# switch_board.net
KiCad netlist of a schematic drawn in EAGLE
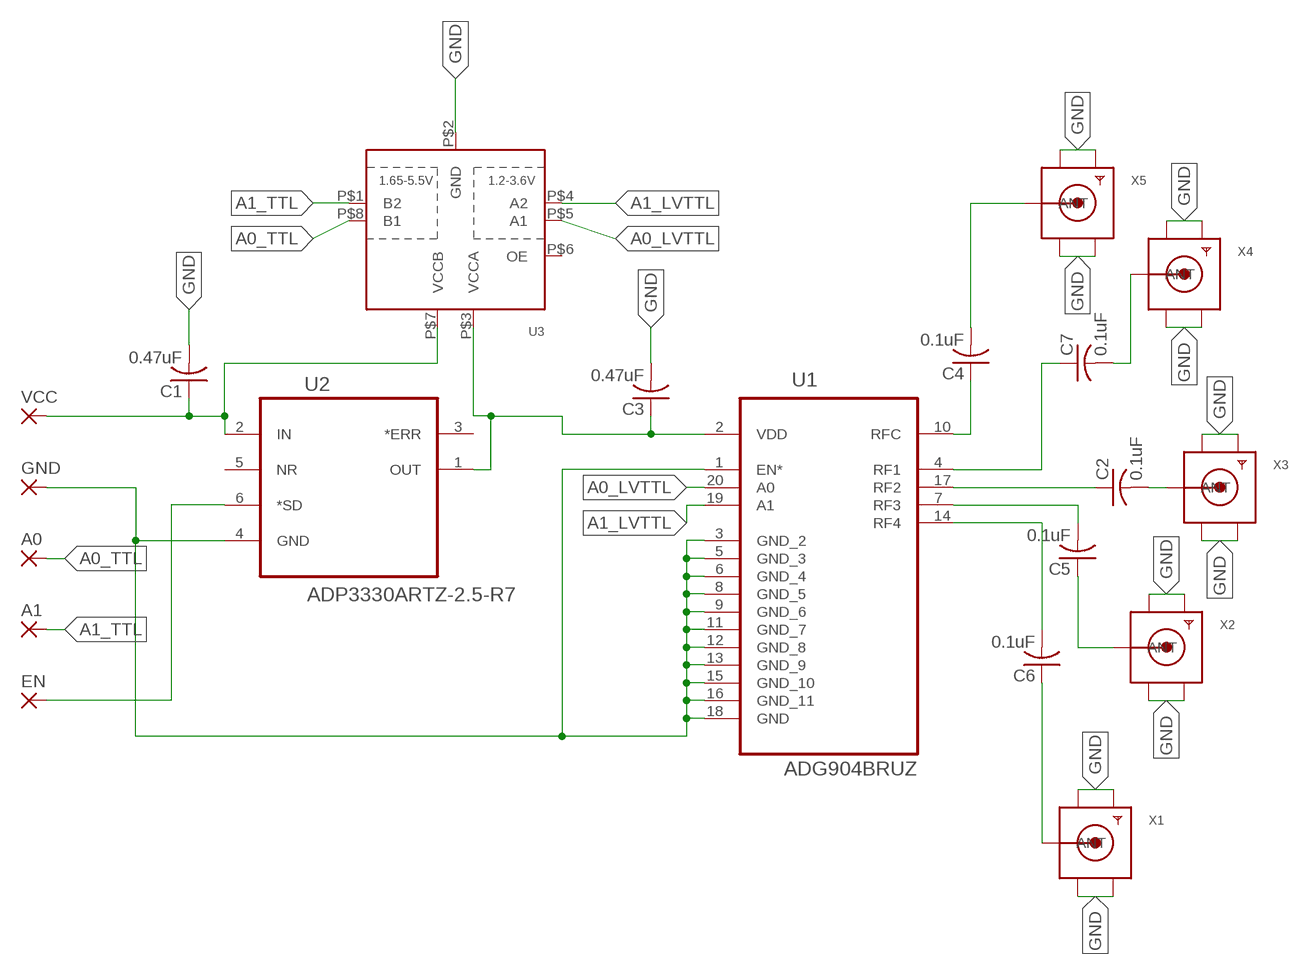
[diagram p0: schematic, sheet 1]

(export (version "E")
  (design (tool "Eeschema 10.0.6"))
  (components
    (comp (ref "A0")
      (value "2,54/1,0")
      (footprint "eagle-import:2,54_1,0")
      (libsource (lib "eagle-import") (part "2,54/1,0"))
    )
    (comp (ref "A1")
      (value "2,54/1,0")
      (footprint "eagle-import:2,54_1,0")
      (libsource (lib "eagle-import") (part "2,54/1,0"))
    )
    (comp (ref "C1")
      (value "0.47uF")
      (footprint "eagle-import:C0603")
      (libsource (lib "eagle-import") (part "C-USC0603"))
    )
    (comp (ref "C2")
      (value "0.1uF")
      (footprint "eagle-import:C0603")
      (libsource (lib "eagle-import") (part "C-USC0603"))
    )
    (comp (ref "C3")
      (value "0.47uF")
      (footprint "eagle-import:C0603")
      (libsource (lib "eagle-import") (part "C-USC0603"))
    )
    (comp (ref "C4")
      (value "0.1uF")
      (footprint "eagle-import:C0603")
      (libsource (lib "eagle-import") (part "C-USC0603"))
    )
    (comp (ref "C5")
      (value "0.1uF")
      (footprint "eagle-import:C0603")
      (libsource (lib "eagle-import") (part "C-USC0603"))
    )
    (comp (ref "C6")
      (value "0.1uF")
      (footprint "eagle-import:C0603")
      (libsource (lib "eagle-import") (part "C-USC0603"))
    )
    (comp (ref "C7")
      (value "0.1uF")
      (footprint "eagle-import:C0603")
      (libsource (lib "eagle-import") (part "C-USC0603"))
    )
    (comp (ref "EN")
      (value "2,54/1,0")
      (footprint "eagle-import:2,54_1,0")
      (libsource (lib "eagle-import") (part "2,54/1,0"))
    )
    (comp (ref "GND")
      (value "2,54/1,0")
      (footprint "eagle-import:2,54_1,0")
      (libsource (lib "eagle-import") (part "2,54/1,0"))
    )
    (comp (ref "U1")
      (value "ADG904BRUZ")
      (footprint "eagle-import:SOP65P640X120-20N")
      (libsource (lib "eagle-import") (part "ADG904BRUZ"))
    )
    (comp (ref "U2")
      (value "ADP3330ARTZ-2.5-R7")
      (footprint "eagle-import:SOT95P280X145-6N")
      (libsource (lib "eagle-import") (part "ADP3330ARTZ-2.5-R7"))
    )
    (comp (ref "U3")
      (value "TXS0102")
      (footprint "eagle-import:VFSOP-8")
      (libsource (lib "eagle-import") (part "TXS0102"))
    )
    (comp (ref "VCC")
      (value "2,54/1,0")
      (footprint "eagle-import:2,54_1,0")
      (libsource (lib "eagle-import") (part "2,54/1,0"))
    )
    (comp (ref "X1")
      (value "SMACONNECTOR_EDGE")
      (footprint "eagle-import:SMA_EDGELAUNCH")
      (libsource (lib "eagle-import") (part "SMACONNECTOR_EDGE"))
    )
    (comp (ref "X2")
      (value "SMACONNECTOR_EDGE")
      (footprint "eagle-import:SMA_EDGELAUNCH")
      (libsource (lib "eagle-import") (part "SMACONNECTOR_EDGE"))
    )
    (comp (ref "X3")
      (value "SMACONNECTOR_EDGE")
      (footprint "eagle-import:SMA_EDGELAUNCH")
      (libsource (lib "eagle-import") (part "SMACONNECTOR_EDGE"))
    )
    (comp (ref "X4")
      (value "SMACONNECTOR_EDGE")
      (footprint "eagle-import:SMA_EDGELAUNCH")
      (libsource (lib "eagle-import") (part "SMACONNECTOR_EDGE"))
    )
    (comp (ref "X5")
      (value "SMACONNECTOR_EDGE")
      (footprint "eagle-import:SMA_EDGELAUNCH")
      (libsource (lib "eagle-import") (part "SMACONNECTOR_EDGE"))
    )
  )
  (nets
    (net (code "1") (name "A0_LVTTL") (class "Default")
      (node (ref "U1") (pin "20") (pinfunction "A0_20") (pintype "passive"))
      (node (ref "U3") (pin "P$5") (pinfunction "A1_P$5") (pintype "bidirectional"))
    )
    (net (code "2") (name "A0_TTL") (class "Default")
      (node (ref "A0") (pin "1") (pinfunction "P_1") (pintype "passive"))
      (node (ref "U3") (pin "P$8") (pinfunction "B1_P$8") (pintype "bidirectional"))
    )
    (net (code "3") (name "A1_LVTTL") (class "Default")
      (node (ref "U1") (pin "19") (pinfunction "A1_19") (pintype "passive"))
      (node (ref "U3") (pin "P$4") (pinfunction "A2_P$4") (pintype "bidirectional"))
    )
    (net (code "4") (name "A1_TTL") (class "Default")
      (node (ref "A1") (pin "1") (pinfunction "P_1") (pintype "passive"))
      (node (ref "U3") (pin "P$1") (pinfunction "B2_P$1") (pintype "bidirectional"))
    )
    (net (code "5") (name "GND") (class "Default")
      (node (ref "C1") (pin "2") (pinfunction "2_2") (pintype "passive"))
      (node (ref "C3") (pin "2") (pinfunction "2_2") (pintype "passive"))
      (node (ref "GND") (pin "1") (pinfunction "P_1") (pintype "passive"))
      (node (ref "U1") (pin "1") (pinfunction "EN*_1") (pintype "passive"))
      (node (ref "U1") (pin "11") (pinfunction "GND_7_11") (pintype "passive"))
      (node (ref "U1") (pin "12") (pinfunction "GND_8_12") (pintype "passive"))
      (node (ref "U1") (pin "13") (pinfunction "GND_9_13") (pintype "passive"))
      (node (ref "U1") (pin "15") (pinfunction "GND_10_15") (pintype "passive"))
      (node (ref "U1") (pin "16") (pinfunction "GND_11_16") (pintype "passive"))
      (node (ref "U1") (pin "18") (pinfunction "GND_18") (pintype "passive"))
      (node (ref "U1") (pin "3") (pinfunction "GND_2_3") (pintype "passive"))
      (node (ref "U1") (pin "5") (pinfunction "GND_3_5") (pintype "passive"))
      (node (ref "U1") (pin "6") (pinfunction "GND_4_6") (pintype "passive"))
      (node (ref "U1") (pin "8") (pinfunction "GND_5_8") (pintype "passive"))
      (node (ref "U1") (pin "9") (pinfunction "GND_6_9") (pintype "passive"))
      (node (ref "U2") (pin "4") (pinfunction "GND_4") (pintype "output"))
      (node (ref "U3") (pin "P$2") (pinfunction "GND_P$2") (pintype "bidirectional"))
      (node (ref "X1") (pin "GND@1") (pinfunction "GND4_GND@1") (pintype "power_in"))
      (node (ref "X1") (pin "GND@2") (pinfunction "GND3_GND@2") (pintype "power_in"))
      (node (ref "X1") (pin "GND@3") (pinfunction "GND2_GND@3") (pintype "power_in"))
      (node (ref "X1") (pin "GND@4") (pinfunction "GND1_GND@4") (pintype "power_in"))
      (node (ref "X2") (pin "GND@1") (pinfunction "GND4_GND@1") (pintype "power_in"))
      (node (ref "X2") (pin "GND@2") (pinfunction "GND3_GND@2") (pintype "power_in"))
      (node (ref "X2") (pin "GND@3") (pinfunction "GND2_GND@3") (pintype "power_in"))
      (node (ref "X2") (pin "GND@4") (pinfunction "GND1_GND@4") (pintype "power_in"))
      (node (ref "X3") (pin "GND@1") (pinfunction "GND4_GND@1") (pintype "power_in"))
      (node (ref "X3") (pin "GND@2") (pinfunction "GND3_GND@2") (pintype "power_in"))
      (node (ref "X3") (pin "GND@3") (pinfunction "GND2_GND@3") (pintype "power_in"))
      (node (ref "X3") (pin "GND@4") (pinfunction "GND1_GND@4") (pintype "power_in"))
      (node (ref "X4") (pin "GND@1") (pinfunction "GND4_GND@1") (pintype "power_in"))
      (node (ref "X4") (pin "GND@2") (pinfunction "GND3_GND@2") (pintype "power_in"))
      (node (ref "X4") (pin "GND@3") (pinfunction "GND2_GND@3") (pintype "power_in"))
      (node (ref "X4") (pin "GND@4") (pinfunction "GND1_GND@4") (pintype "power_in"))
      (node (ref "X5") (pin "GND@1") (pinfunction "GND4_GND@1") (pintype "power_in"))
      (node (ref "X5") (pin "GND@2") (pinfunction "GND3_GND@2") (pintype "power_in"))
      (node (ref "X5") (pin "GND@3") (pinfunction "GND2_GND@3") (pintype "power_in"))
      (node (ref "X5") (pin "GND@4") (pinfunction "GND1_GND@4") (pintype "power_in"))
    )
    (net (code "6") (name "Net-(EN-P)") (class "Default")
      (node (ref "EN") (pin "1") (pinfunction "P_1") (pintype "passive"))
      (node (ref "U2") (pin "6") (pinfunction "*SD_6") (pintype "output"))
    )
    (net (code "7") (name "Net-(U1-RF1)") (class "Default")
      (node (ref "C7") (pin "1") (pinfunction "1_1") (pintype "passive"))
      (node (ref "U1") (pin "4") (pinfunction "RF1_4") (pintype "passive"))
    )
    (net (code "8") (name "Net-(U1-RF2)") (class "Default")
      (node (ref "C2") (pin "1") (pinfunction "1_1") (pintype "passive"))
      (node (ref "U1") (pin "17") (pinfunction "RF2_17") (pintype "passive"))
    )
    (net (code "9") (name "Net-(U1-RF3)") (class "Default")
      (node (ref "C5") (pin "2") (pinfunction "2_2") (pintype "passive"))
      (node (ref "U1") (pin "7") (pinfunction "RF3_7") (pintype "passive"))
    )
    (net (code "10") (name "Net-(U1-RF4)") (class "Default")
      (node (ref "C6") (pin "2") (pinfunction "2_2") (pintype "passive"))
      (node (ref "U1") (pin "14") (pinfunction "RF4_14") (pintype "passive"))
    )
    (net (code "11") (name "Net-(U1-RFC)") (class "Default")
      (node (ref "C4") (pin "1") (pinfunction "1_1") (pintype "passive"))
      (node (ref "U1") (pin "10") (pinfunction "RFC_10") (pintype "passive"))
    )
    (net (code "12") (name "Net-(U1-VDD)") (class "Default")
      (node (ref "C3") (pin "1") (pinfunction "1_1") (pintype "passive"))
      (node (ref "U1") (pin "2") (pinfunction "VDD_2") (pintype "power_in"))
      (node (ref "U2") (pin "1") (pinfunction "OUT_1") (pintype "passive"))
      (node (ref "U3") (pin "P$3") (pinfunction "VCCA_P$3") (pintype "bidirectional"))
    )
    (net (code "13") (name "Net-(U2-IN)") (class "Default")
      (node (ref "C1") (pin "1") (pinfunction "1_1") (pintype "passive"))
      (node (ref "U2") (pin "2") (pinfunction "IN_2") (pintype "passive"))
      (node (ref "U3") (pin "P$7") (pinfunction "VCCB_P$7") (pintype "bidirectional"))
      (node (ref "VCC") (pin "1") (pinfunction "P_1") (pintype "passive"))
    )
    (net (code "14") (name "Net-(X1-ANT)") (class "Default")
      (node (ref "C6") (pin "1") (pinfunction "1_1") (pintype "passive"))
      (node (ref "X1") (pin "P") (pinfunction "ANT_P") (pintype "bidirectional"))
    )
    (net (code "15") (name "Net-(X2-ANT)") (class "Default")
      (node (ref "C5") (pin "1") (pinfunction "1_1") (pintype "passive"))
      (node (ref "X2") (pin "P") (pinfunction "ANT_P") (pintype "bidirectional"))
    )
    (net (code "16") (name "Net-(X3-ANT)") (class "Default")
      (node (ref "C2") (pin "2") (pinfunction "2_2") (pintype "passive"))
      (node (ref "X3") (pin "P") (pinfunction "ANT_P") (pintype "bidirectional"))
    )
    (net (code "17") (name "Net-(X4-ANT)") (class "Default")
      (node (ref "C7") (pin "2") (pinfunction "2_2") (pintype "passive"))
      (node (ref "X4") (pin "P") (pinfunction "ANT_P") (pintype "bidirectional"))
    )
    (net (code "18") (name "Net-(X5-ANT)") (class "Default")
      (node (ref "C4") (pin "2") (pinfunction "2_2") (pintype "passive"))
      (node (ref "X5") (pin "P") (pinfunction "ANT_P") (pintype "bidirectional"))
    )
    (net (code "19") (name "unconnected-(U2-*ERR-Pad3)") (class "Default")
      (node (ref "U2") (pin "3") (pinfunction "*ERR_3") (pintype "passive"))
    )
    (net (code "20") (name "unconnected-(U2-NR-Pad5)") (class "Default")
      (node (ref "U2") (pin "5") (pinfunction "NR_5") (pintype "input"))
    )
    (net (code "21") (name "unconnected-(U3-OE-PadP$6)") (class "Default")
      (node (ref "U3") (pin "P$6") (pinfunction "OE_P$6") (pintype "bidirectional"))
    )
  )
)
